# H4RG_Preamp.net
KiCad netlist of a schematic drawn in Altium Designer
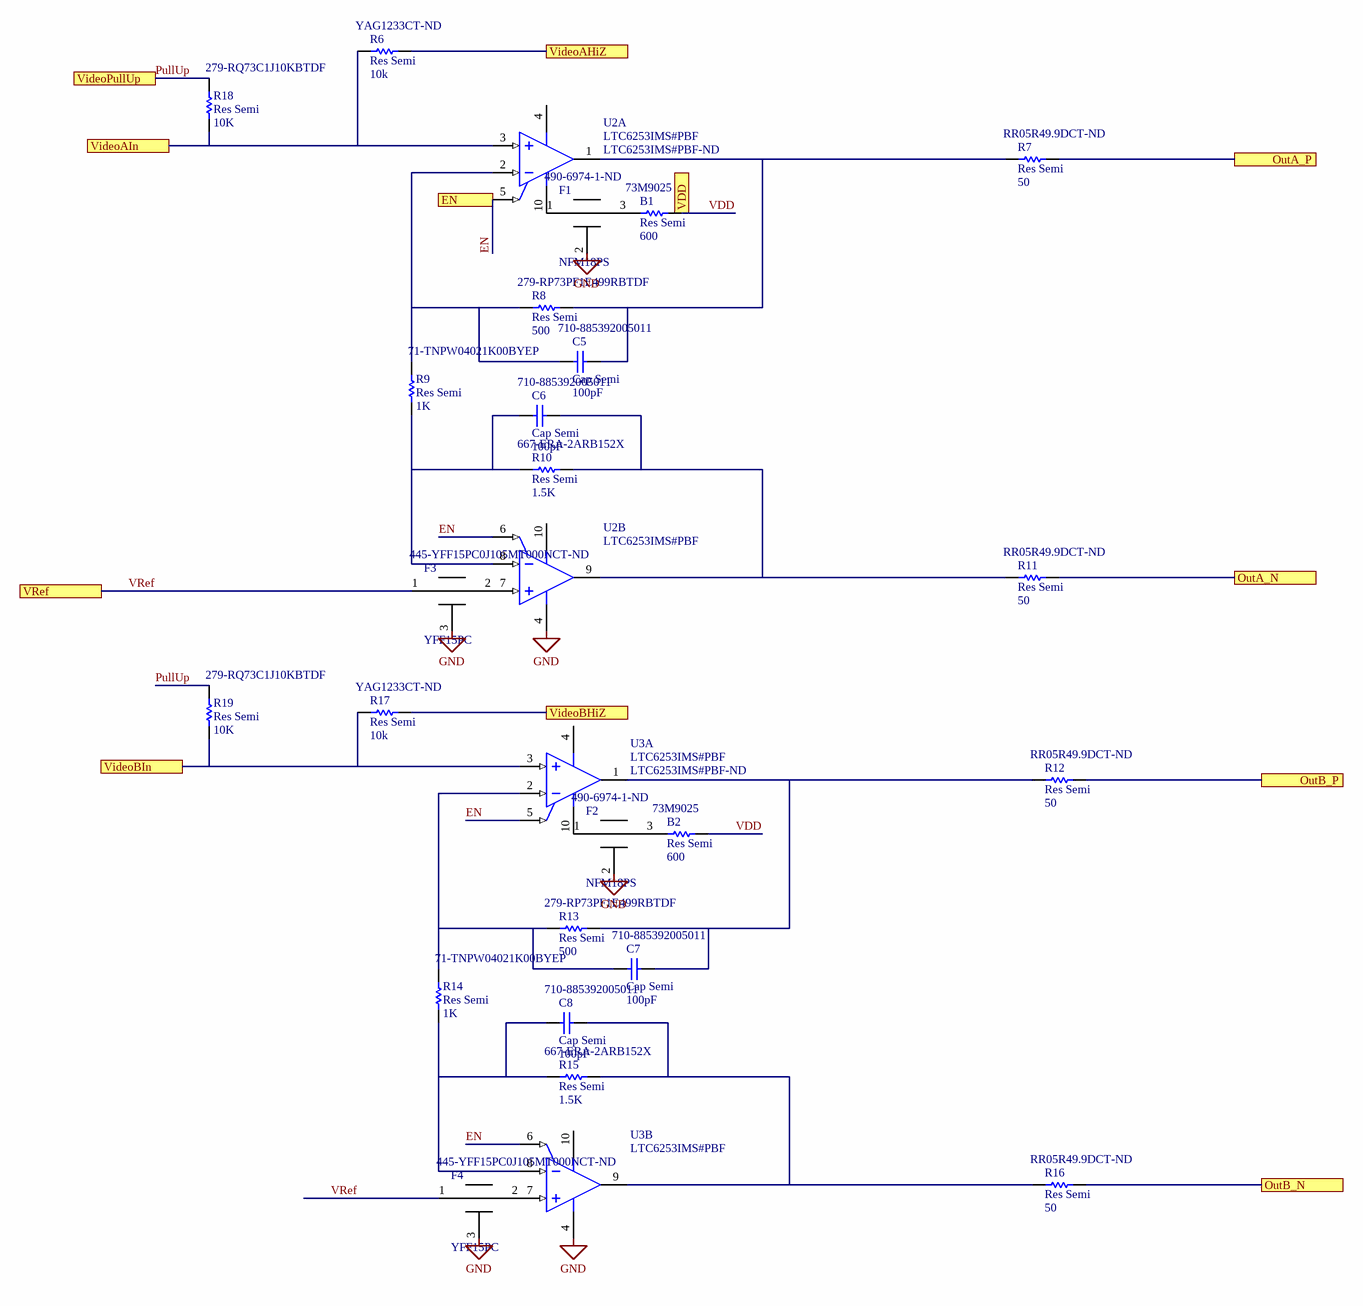
[diagram p0: H4RG_Preamp.SchDoc]

(export (version "E")
  (design (tool "Eeschema 10.0.6"))
  (components
    (comp (ref "B1")
      (value "Res Semi")
      (footprint "RESC1005X04N")
      (description "FERRITE BEAD 600 OHM 0402 1LN")
      (fields
        (field (name "ALTIUM_VALUE") "600")
        (field (name "SUPPLIER PART NUMBER 1") "73M9025")
        (field (name "TOLERANCE") "25%")
        (field (name "PUBLISHER") "Altium Limited")
      )
      (libsource (lib "Miscellaneous Devices") (part "Res Semi"))
    )
    (comp (ref "B2")
      (value "Res Semi")
      (footprint "RESC1005X04N")
      (description "FERRITE BEAD 600 OHM 0402 1LN")
      (fields
        (field (name "ALTIUM_VALUE") "600")
        (field (name "SUPPLIER PART NUMBER 1") "73M9025")
        (field (name "TOLERANCE") "25%")
        (field (name "PUBLISHER") "Altium Limited")
      )
      (libsource (lib "Miscellaneous Devices") (part "Res Semi"))
    )
    (comp (ref "C5")
      (value "Cap Semi")
      (footprint "CAPC1005X06L")
      (description "Cap, 3.3Pf, 50V, Rf Mlcc, 0402")
      (fields
        (field (name "ALTIUM_VALUE") "100pF")
        (field (name "SUPPLIER PART NUMBER 1") "710-885392005011")
        (field (name "PUBLISHER") "Altium Limited")
      )
      (libsource (lib "Miscellaneous Devices") (part "Cap Semi"))
    )
    (comp (ref "C6")
      (value "Cap Semi")
      (footprint "CAPC1005X06L")
      (description "Cap, 3.3Pf, 50V, Rf Mlcc, 0402")
      (fields
        (field (name "ALTIUM_VALUE") "100pF")
        (field (name "SUPPLIER PART NUMBER 1") "710-885392005011")
        (field (name "PUBLISHER") "Altium Limited")
      )
      (libsource (lib "Miscellaneous Devices") (part "Cap Semi"))
    )
    (comp (ref "C7")
      (value "Cap Semi")
      (footprint "CAPC1005X06L")
      (description "Cap, 3.3Pf, 50V, Rf Mlcc, 0402")
      (fields
        (field (name "ALTIUM_VALUE") "100pF")
        (field (name "SUPPLIER PART NUMBER 1") "710-885392005011")
        (field (name "PUBLISHER") "Altium Limited")
      )
      (libsource (lib "Miscellaneous Devices") (part "Cap Semi"))
    )
    (comp (ref "C8")
      (value "Cap Semi")
      (footprint "CAPC1005X06L")
      (description "Cap, 3.3Pf, 50V, Rf Mlcc, 0402")
      (fields
        (field (name "ALTIUM_VALUE") "100pF")
        (field (name "SUPPLIER PART NUMBER 1") "710-885392005011")
        (field (name "PUBLISHER") "Altium Limited")
      )
      (libsource (lib "Miscellaneous Devices") (part "Cap Semi"))
    )
    (comp (ref "F1")
      (value "NFM18PS")
      (footprint "NFM18PS_0603")
      (description "CAP FEEDTHRU 1UF 20% 6.3V 0603")
      (fields
        (field (name "SUPPLIER PART NUMBER 1") "490-6974-1-ND")
        (field (name "TOLERANCE") "20%")
        (field (name "VOLTAGE") "6.3V")
      )
      (libsource (lib "NFM18PS") (part "NFM18PS"))
    )
    (comp (ref "F2")
      (value "NFM18PS")
      (footprint "NFM18PS_0603")
      (description "CAP FEEDTHRU 1UF 20% 6.3V 0603")
      (fields
        (field (name "SUPPLIER PART NUMBER 1") "490-6974-1-ND")
        (field (name "TOLERANCE") "20%")
        (field (name "VOLTAGE") "6.3V")
      )
      (libsource (lib "NFM18PS") (part "NFM18PS"))
    )
    (comp (ref "F3")
      (value "YFF15PC")
      (footprint "YFF15PC")
      (description "Feedthrough Capacitor, 1UF, 4V, 0402;")
      (fields (field (name "SUPPLIER PART NUMBER 1") "445-YFF15PC0J105MT000NCT-ND"))
      (libsource (lib "FTCap") (part "YFF15PC"))
    )
    (comp (ref "F4")
      (value "YFF15PC")
      (footprint "YFF15PC")
      (description "Feedthrough Capacitor, 1UF, 4V, 0402;")
      (fields (field (name "SUPPLIER PART NUMBER 1") "445-YFF15PC0J105MT000NCT-ND"))
      (libsource (lib "FTCap") (part "YFF15PC"))
    )
    (comp (ref "R6")
      (value "Res Semi")
      (footprint "RESC1005X04N")
      (fields
        (field (name "ALTIUM_VALUE") "10k")
        (field (name "SUPPLIER PART NUMBER 1") "YAG1233CT-ND")
        (field (name "TOLERANCE") "1%")
        (field (name "PUBLISHER") "Altium Limited")
      )
      (libsource (lib "Miscellaneous Devices") (part "Res Semi"))
    )
    (comp (ref "R7")
      (value "Res Semi")
      (footprint "RESC1005X04N")
      (description "SUSUMU - RR0510R-49R9-D - RES, THIN FILM, 49R9, 0.5%, 0.0625W, 0402")
      (fields
        (field (name "ALTIUM_VALUE") "50")
        (field (name "SUPPLIER PART NUMBER 1") "RR05R49.9DCT-ND")
        (field (name "TOLERANCE") "0.5%")
        (field (name "PUBLISHER") "Altium Limited")
      )
      (libsource (lib "Miscellaneous Devices") (part "Res Semi"))
    )
    (comp (ref "R8")
      (value "Res Semi")
      (footprint "RESC1005X04N")
      (description "Res Thin Film 0402 499 Ohm 0.1% 0.1W(1/10W) ±25ppm/C Pad SMD T/R")
      (fields
        (field (name "ALTIUM_VALUE") "500")
        (field (name "SUPPLIER PART NUMBER 1") "279-RP73PF1E499RBTDF")
        (field (name "PUBLISHER") "Altium Limited")
      )
      (libsource (lib "Miscellaneous Devices") (part "Res Semi"))
    )
    (comp (ref "R9")
      (value "Res Semi")
      (footprint "RESC1005X04N")
      (fields
        (field (name "ALTIUM_VALUE") "1K")
        (field (name "SUPPLIER PART NUMBER 1") "71-TNPW04021K00BYEP")
        (field (name "TOLERANCE") "0.1%")
        (field (name "PUBLISHER") "Altium Limited")
      )
      (libsource (lib "Miscellaneous Devices") (part "Res Semi"))
    )
    (comp (ref "R10")
      (value "Res Semi")
      (footprint "RESC1005X04N")
      (description "RES SMD 1.5K OHM 0.1% 1/16W 0402")
      (fields
        (field (name "ALTIUM_VALUE") "1.5K")
        (field (name "SUPPLIER PART NUMBER 1") "667-ERA-2ARB152X")
        (field (name "TOLERANCE") "0.1%")
        (field (name "PUBLISHER") "Altium Limited")
      )
      (libsource (lib "Miscellaneous Devices") (part "Res Semi"))
    )
    (comp (ref "R11")
      (value "Res Semi")
      (footprint "RESC1005X04N")
      (description "SUSUMU - RR0510R-49R9-D - RES, THIN FILM, 49R9, 0.5%, 0.0625W, 0402")
      (fields
        (field (name "ALTIUM_VALUE") "50")
        (field (name "SUPPLIER PART NUMBER 1") "RR05R49.9DCT-ND")
        (field (name "TOLERANCE") "0.5%")
        (field (name "PUBLISHER") "Altium Limited")
      )
      (libsource (lib "Miscellaneous Devices") (part "Res Semi"))
    )
    (comp (ref "R12")
      (value "Res Semi")
      (footprint "RESC1005X04N")
      (description "SUSUMU - RR0510R-49R9-D - RES, THIN FILM, 49R9, 0.5%, 0.0625W, 0402")
      (fields
        (field (name "ALTIUM_VALUE") "50")
        (field (name "SUPPLIER PART NUMBER 1") "RR05R49.9DCT-ND")
        (field (name "TOLERANCE") "0.5%")
        (field (name "PUBLISHER") "Altium Limited")
      )
      (libsource (lib "Miscellaneous Devices") (part "Res Semi"))
    )
    (comp (ref "R13")
      (value "Res Semi")
      (footprint "RESC1005X04N")
      (description "Res Thin Film 0402 499 Ohm 0.1% 0.1W(1/10W) ±25ppm/C Pad SMD T/R")
      (fields
        (field (name "ALTIUM_VALUE") "500")
        (field (name "SUPPLIER PART NUMBER 1") "279-RP73PF1E499RBTDF")
        (field (name "PUBLISHER") "Altium Limited")
      )
      (libsource (lib "Miscellaneous Devices") (part "Res Semi"))
    )
    (comp (ref "R14")
      (value "Res Semi")
      (footprint "RESC1005X04N")
      (fields
        (field (name "ALTIUM_VALUE") "1K")
        (field (name "SUPPLIER PART NUMBER 1") "71-TNPW04021K00BYEP")
        (field (name "TOLERANCE") "0.1%")
        (field (name "PUBLISHER") "Altium Limited")
      )
      (libsource (lib "Miscellaneous Devices") (part "Res Semi"))
    )
    (comp (ref "R15")
      (value "Res Semi")
      (footprint "RESC1005X04N")
      (description "RES SMD 1.5K OHM 0.1% 1/16W 0402")
      (fields
        (field (name "ALTIUM_VALUE") "1.5K")
        (field (name "SUPPLIER PART NUMBER 1") "667-ERA-2ARB152X")
        (field (name "TOLERANCE") "0.1%")
        (field (name "PUBLISHER") "Altium Limited")
      )
      (libsource (lib "Miscellaneous Devices") (part "Res Semi"))
    )
    (comp (ref "R16")
      (value "Res Semi")
      (footprint "RESC1005X04N")
      (description "SUSUMU - RR0510R-49R9-D - RES, THIN FILM, 49R9, 0.5%, 0.0625W, 0402")
      (fields
        (field (name "ALTIUM_VALUE") "50")
        (field (name "SUPPLIER PART NUMBER 1") "RR05R49.9DCT-ND")
        (field (name "TOLERANCE") "0.5%")
        (field (name "PUBLISHER") "Altium Limited")
      )
      (libsource (lib "Miscellaneous Devices") (part "Res Semi"))
    )
    (comp (ref "R17")
      (value "Res Semi")
      (footprint "RESC1005X04N")
      (fields
        (field (name "ALTIUM_VALUE") "10k")
        (field (name "SUPPLIER PART NUMBER 1") "YAG1233CT-ND")
        (field (name "TOLERANCE") "1%")
        (field (name "PUBLISHER") "Altium Limited")
      )
      (libsource (lib "Miscellaneous Devices") (part "Res Semi"))
    )
    (comp (ref "R18")
      (value "Res Semi")
      (footprint "Res0603LD")
      (description "Res SMD 10K Ohm 0.01% 0.15W 0603")
      (fields
        (field (name "ALTIUM_VALUE") "10K")
        (field (name "TOLERANCE") "0.01%")
        (field (name "SUPPLIER PART NUMBER 1") "279-RQ73C1J10KBTDF")
        (field (name "PUBLISHER") "Altium Limited")
      )
      (libsource (lib "Miscellaneous Devices") (part "Res Semi"))
    )
    (comp (ref "R19")
      (value "Res Semi")
      (footprint "Res0603LD")
      (description "Res SMD 10K Ohm 0.01% 0.15W 0603")
      (fields
        (field (name "ALTIUM_VALUE") "10K")
        (field (name "TOLERANCE") "0.01%")
        (field (name "SUPPLIER PART NUMBER 1") "279-RQ73C1J10KBTDF")
        (field (name "PUBLISHER") "Altium Limited")
      )
      (libsource (lib "Miscellaneous Devices") (part "Res Semi"))
    )
    (comp (ref "U2")
      (value "LTC6253IMS#PBF")
      (footprint "LT-MS-10_N")
      (fields
        (field (name "LINEAR TECHNOLOGY PART NUMBER") "LTC6253")
        (field (name "MANUFACTURER") "Linear Technology")
        (field (name "SUPPLIER PART NUMBER 1") "LTC6253IMS#PBF-ND")
      )
      (libsource (lib "Altium Content Vault") (part "LT-LTC6253-MS-10"))
    )
    (comp (ref "U3")
      (value "LTC6253IMS#PBF")
      (footprint "LT-MS-10_N")
      (fields
        (field (name "LINEAR TECHNOLOGY PART NUMBER") "LTC6253")
        (field (name "MANUFACTURER") "Linear Technology")
        (field (name "SUPPLIER PART NUMBER 1") "LTC6253IMS#PBF-ND")
      )
      (libsource (lib "Altium Content Vault") (part "LT-LTC6253-MS-10"))
    )
  )
  (nets
    (net (code "1") (name "/EN") (class "Default")
      (node (ref "U2") (pin "5") (pinfunction "~{SHDNA}_5") (pintype "input"))
      (node (ref "U2") (pin "6") (pinfunction "~{SHDNB}_6") (pintype "input"))
      (node (ref "U3") (pin "5") (pinfunction "~{SHDNA}_5") (pintype "input"))
      (node (ref "U3") (pin "6") (pinfunction "~{SHDNB}_6") (pintype "input"))
    )
    (net (code "2") (name "/OutA_N") (class "Default")
      (node (ref "R11") (pin "2") (pinfunction "2_2") (pintype "passive"))
    )
    (net (code "3") (name "/OutA_P") (class "Default")
      (node (ref "R7") (pin "2") (pinfunction "2_2") (pintype "passive"))
    )
    (net (code "4") (name "/OutB_N") (class "Default")
      (node (ref "R16") (pin "2") (pinfunction "2_2") (pintype "passive"))
    )
    (net (code "5") (name "/OutB_P") (class "Default")
      (node (ref "R12") (pin "2") (pinfunction "2_2") (pintype "passive"))
    )
    (net (code "6") (name "/PullUp") (class "Default")
      (node (ref "R18") (pin "2") (pinfunction "2_2") (pintype "passive"))
      (node (ref "R19") (pin "2") (pinfunction "2_2") (pintype "passive"))
    )
    (net (code "7") (name "/VDD") (class "Default")
      (node (ref "B1") (pin "2") (pinfunction "2_2") (pintype "passive"))
      (node (ref "B2") (pin "2") (pinfunction "2_2") (pintype "passive"))
    )
    (net (code "8") (name "/VRef") (class "Default")
      (node (ref "F3") (pin "1") (pinfunction "1_1") (pintype "passive"))
      (node (ref "F4") (pin "1") (pinfunction "1_1") (pintype "passive"))
    )
    (net (code "9") (name "/VideoAHiZ") (class "Default")
      (node (ref "R6") (pin "2") (pinfunction "2_2") (pintype "passive"))
    )
    (net (code "10") (name "/VideoAIn") (class "Default")
      (node (ref "R18") (pin "1") (pinfunction "1_1") (pintype "passive"))
      (node (ref "R6") (pin "1") (pinfunction "1_1") (pintype "passive"))
      (node (ref "U2") (pin "3") (pinfunction "+IN_A_3") (pintype "input"))
    )
    (net (code "11") (name "/VideoBHiZ") (class "Default")
      (node (ref "R17") (pin "2") (pinfunction "2_2") (pintype "passive"))
    )
    (net (code "12") (name "/VideoBIn") (class "Default")
      (node (ref "R17") (pin "1") (pinfunction "1_1") (pintype "passive"))
      (node (ref "R19") (pin "1") (pinfunction "1_1") (pintype "passive"))
      (node (ref "U3") (pin "3") (pinfunction "+IN_A_3") (pintype "input"))
    )
    (net (code "13") (name "GND") (class "Default")
      (node (ref "F1") (pin "2") (pinfunction "2_2") (pintype "passive"))
      (node (ref "F2") (pin "2") (pinfunction "2_2") (pintype "passive"))
      (node (ref "F3") (pin "3") (pinfunction "3_3") (pintype "passive"))
      (node (ref "F4") (pin "3") (pinfunction "3_3") (pintype "passive"))
      (node (ref "U2") (pin "4") (pinfunction "V-_4") (pintype "power_in"))
      (node (ref "U3") (pin "4") (pinfunction "V-_4") (pintype "power_in"))
    )
    (net (code "14") (name "Net-(B1-Pad1)") (class "Default")
      (node (ref "B1") (pin "1") (pinfunction "1_1") (pintype "passive"))
      (node (ref "F1") (pin "3") (pinfunction "3_3") (pintype "passive"))
    )
    (net (code "15") (name "Net-(B2-Pad1)") (class "Default")
      (node (ref "B2") (pin "1") (pinfunction "1_1") (pintype "passive"))
      (node (ref "F2") (pin "3") (pinfunction "3_3") (pintype "passive"))
    )
    (net (code "16") (name "Net-(U2A--IN_A)") (class "Default")
      (node (ref "C5") (pin "1") (pinfunction "1_1") (pintype "passive"))
      (node (ref "R8") (pin "2") (pinfunction "2_2") (pintype "passive"))
      (node (ref "R9") (pin "2") (pinfunction "2_2") (pintype "passive"))
      (node (ref "U2") (pin "2") (pinfunction "-IN_A_2") (pintype "input"))
    )
    (net (code "17") (name "Net-(U2A-OUT_A)") (class "Default")
      (node (ref "C5") (pin "2") (pinfunction "2_2") (pintype "passive"))
      (node (ref "R7") (pin "1") (pinfunction "1_1") (pintype "passive"))
      (node (ref "R8") (pin "1") (pinfunction "1_1") (pintype "passive"))
      (node (ref "U2") (pin "1") (pinfunction "OUT_A_1") (pintype "tri_state"))
    )
    (net (code "18") (name "Net-(U2A-V+)") (class "Default")
      (node (ref "F1") (pin "1") (pinfunction "1_1") (pintype "passive"))
      (node (ref "U2") (pin "10") (pinfunction "V+_10") (pintype "power_in"))
    )
    (net (code "19") (name "Net-(U2B-+IN_B)") (class "Default")
      (node (ref "F3") (pin "2") (pinfunction "2_2") (pintype "passive"))
      (node (ref "U2") (pin "7") (pinfunction "+IN_B_7") (pintype "input"))
    )
    (net (code "20") (name "Net-(U2B--IN_B)") (class "Default")
      (node (ref "C6") (pin "1") (pinfunction "1_1") (pintype "passive"))
      (node (ref "R10") (pin "1") (pinfunction "1_1") (pintype "passive"))
      (node (ref "R9") (pin "1") (pinfunction "1_1") (pintype "passive"))
      (node (ref "U2") (pin "8") (pinfunction "-IN_B_8") (pintype "input"))
    )
    (net (code "21") (name "Net-(U2B-OUT_B)") (class "Default")
      (node (ref "C6") (pin "2") (pinfunction "2_2") (pintype "passive"))
      (node (ref "R10") (pin "2") (pinfunction "2_2") (pintype "passive"))
      (node (ref "R11") (pin "1") (pinfunction "1_1") (pintype "passive"))
      (node (ref "U2") (pin "9") (pinfunction "OUT_B_9") (pintype "tri_state"))
    )
    (net (code "22") (name "Net-(U3A--IN_A)") (class "Default")
      (node (ref "C7") (pin "1") (pinfunction "1_1") (pintype "passive"))
      (node (ref "R13") (pin "2") (pinfunction "2_2") (pintype "passive"))
      (node (ref "R14") (pin "2") (pinfunction "2_2") (pintype "passive"))
      (node (ref "U3") (pin "2") (pinfunction "-IN_A_2") (pintype "input"))
    )
    (net (code "23") (name "Net-(U3A-OUT_A)") (class "Default")
      (node (ref "C7") (pin "2") (pinfunction "2_2") (pintype "passive"))
      (node (ref "R12") (pin "1") (pinfunction "1_1") (pintype "passive"))
      (node (ref "R13") (pin "1") (pinfunction "1_1") (pintype "passive"))
      (node (ref "U3") (pin "1") (pinfunction "OUT_A_1") (pintype "tri_state"))
    )
    (net (code "24") (name "Net-(U3A-V+)") (class "Default")
      (node (ref "F2") (pin "1") (pinfunction "1_1") (pintype "passive"))
      (node (ref "U3") (pin "10") (pinfunction "V+_10") (pintype "power_in"))
    )
    (net (code "25") (name "Net-(U3B-+IN_B)") (class "Default")
      (node (ref "F4") (pin "2") (pinfunction "2_2") (pintype "passive"))
      (node (ref "U3") (pin "7") (pinfunction "+IN_B_7") (pintype "input"))
    )
    (net (code "26") (name "Net-(U3B--IN_B)") (class "Default")
      (node (ref "C8") (pin "1") (pinfunction "1_1") (pintype "passive"))
      (node (ref "R14") (pin "1") (pinfunction "1_1") (pintype "passive"))
      (node (ref "R15") (pin "1") (pinfunction "1_1") (pintype "passive"))
      (node (ref "U3") (pin "8") (pinfunction "-IN_B_8") (pintype "input"))
    )
    (net (code "27") (name "Net-(U3B-OUT_B)") (class "Default")
      (node (ref "C8") (pin "2") (pinfunction "2_2") (pintype "passive"))
      (node (ref "R15") (pin "2") (pinfunction "2_2") (pintype "passive"))
      (node (ref "R16") (pin "1") (pinfunction "1_1") (pintype "passive"))
      (node (ref "U3") (pin "9") (pinfunction "OUT_B_9") (pintype "tri_state"))
    )
    (net (code "28") (name "unconnected-(U2A-V--Pad4)") (class "Default")
      (node (ref "U2") (pin "4") (pinfunction "V-_4") (pintype "power_in"))
    )
    (net (code "29") (name "unconnected-(U2B-V+-Pad10)") (class "Default")
      (node (ref "U2") (pin "10") (pinfunction "V+_10") (pintype "power_in"))
    )
    (net (code "30") (name "unconnected-(U3A-V--Pad4)") (class "Default")
      (node (ref "U3") (pin "4") (pinfunction "V-_4") (pintype "power_in"))
    )
    (net (code "31") (name "unconnected-(U3B-V+-Pad10)") (class "Default")
      (node (ref "U3") (pin "10") (pinfunction "V+_10") (pintype "power_in"))
    )
  )
)
